# Telit2XBEE.net
KiCad netlist of a schematic drawn in EAGLE
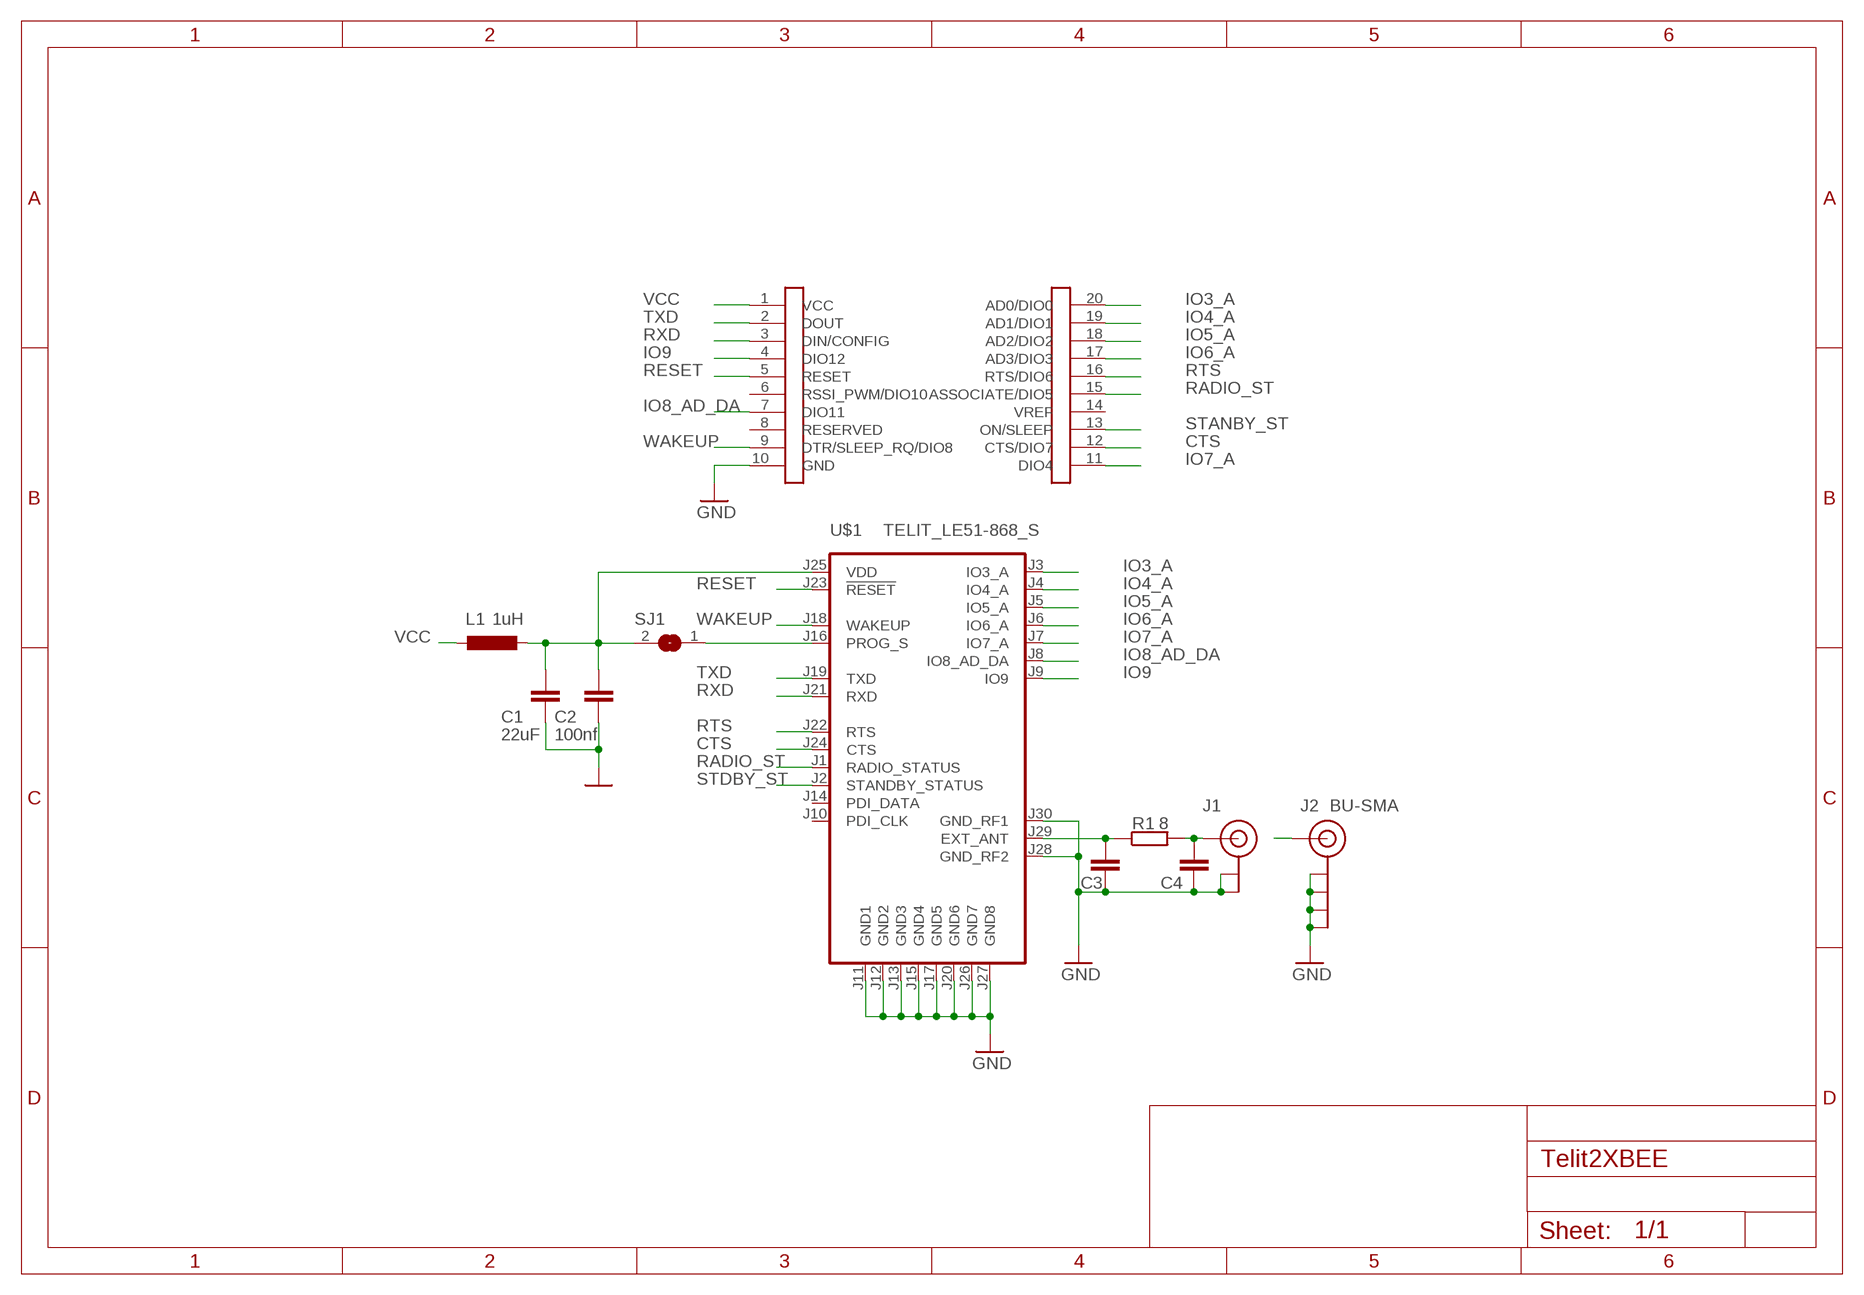
[diagram p0: schematic, sheet 1]

(export (version "E")
  (design (tool "Eeschema 10.0.6"))
  (components
    (comp (ref "C1")
      (value "22uF")
      (footprint "eagle-import:C1206")
      (libsource (lib "eagle-import") (part "C-EUC1206"))
    )
    (comp (ref "C2")
      (value "100nf")
      (footprint "eagle-import:C0805")
      (libsource (lib "eagle-import") (part "C-EUC0805"))
    )
    (comp (ref "C3")
      (value "C-EUC0201")
      (footprint "eagle-import:C0201")
      (libsource (lib "eagle-import") (part "C-EUC0201"))
    )
    (comp (ref "C4")
      (value "C-EUC0201")
      (footprint "eagle-import:C0201")
      (libsource (lib "eagle-import") (part "C-EUC0201"))
    )
    (comp (ref "J1")
      (value "U.FL")
      (footprint "eagle-import:U.FL_1PAD")
      (libsource (lib "eagle-import") (part "U.FL1PAD"))
    )
    (comp (ref "J2")
      (value "BU-SMA")
      (footprint "eagle-import:BU-SMA-G")
      (libsource (lib "eagle-import") (part "BU-SMA"))
    )
    (comp (ref "L1")
      (value "1uH")
      (footprint "eagle-import:COILCRAFT_LPS3015")
      (libsource (lib "eagle-import") (part "POWER_INDUCTOR3"))
    )
    (comp (ref "R1")
      (value "8")
      (footprint "eagle-import:R0201")
      (libsource (lib "eagle-import") (part "R-EU_R0201"))
    )
    (comp (ref "SJ1") (value "SJ") (footprint "eagle-import:SJ") (libsource (lib "eagle-import") (part "SJ")))
    (comp (ref "U$1")
      (value "TELIT_LE51-868_S")
      (footprint "eagle-import:TELIT_LE51")
      (libsource (lib "eagle-import") (part "TELIT_LE51"))
    )
    (comp (ref "U$2")
      (value "XBEE_PIN_HEADER")
      (footprint "eagle-import:XBEE_PIN_HEADER")
      (libsource (lib "eagle-import") (part "XBEE_PIN_HEADER"))
    )
  )
  (nets
    (net (code "1") (name "/CTS") (class "Default")
      (node (ref "U$1") (pin "J24") (pinfunction "CTS_J24") (pintype "bidirectional"))
      (node (ref "U$2") (pin "12") (pinfunction "CTS/DIO7_12") (pintype "bidirectional"))
    )
    (net (code "2") (name "/IO3_A") (class "Default")
      (node (ref "U$1") (pin "J3") (pinfunction "IO3_A_J3") (pintype "bidirectional"))
      (node (ref "U$2") (pin "20") (pinfunction "AD0/DIO0_20") (pintype "bidirectional"))
    )
    (net (code "3") (name "/IO4_A") (class "Default")
      (node (ref "U$1") (pin "J4") (pinfunction "IO4_A_J4") (pintype "bidirectional"))
      (node (ref "U$2") (pin "19") (pinfunction "AD1/DIO1_19") (pintype "bidirectional"))
    )
    (net (code "4") (name "/IO5_A") (class "Default")
      (node (ref "U$1") (pin "J5") (pinfunction "IO5_A_J5") (pintype "bidirectional"))
      (node (ref "U$2") (pin "18") (pinfunction "AD2/DIO2_18") (pintype "bidirectional"))
    )
    (net (code "5") (name "/IO6_A") (class "Default")
      (node (ref "U$1") (pin "J6") (pinfunction "IO6_A_J6") (pintype "bidirectional"))
      (node (ref "U$2") (pin "17") (pinfunction "AD3/DIO3_17") (pintype "bidirectional"))
    )
    (net (code "6") (name "/IO7_A") (class "Default")
      (node (ref "U$1") (pin "J7") (pinfunction "IO7_A_J7") (pintype "bidirectional"))
      (node (ref "U$2") (pin "11") (pinfunction "DIO4_11") (pintype "bidirectional"))
    )
    (net (code "7") (name "/IO8_AD_DA") (class "Default")
      (node (ref "U$1") (pin "J8") (pinfunction "IO8_AD_DA_J8") (pintype "bidirectional"))
      (node (ref "U$2") (pin "7") (pinfunction "DIO11_7") (pintype "bidirectional"))
    )
    (net (code "8") (name "/IO9") (class "Default")
      (node (ref "U$1") (pin "J9") (pinfunction "IO9_J9") (pintype "bidirectional"))
      (node (ref "U$2") (pin "4") (pinfunction "DIO12_4") (pintype "bidirectional"))
    )
    (net (code "9") (name "/N$2") (class "Default")
      (node (ref "C4") (pin "1") (pinfunction "1_1") (pintype "passive"))
      (node (ref "J1") (pin "P$3") (pinfunction "SIGNAL_P$3") (pintype "bidirectional"))
      (node (ref "J2") (pin "P$1") (pinfunction "SIGNAL_P$1") (pintype "bidirectional"))
      (node (ref "R1") (pin "2") (pinfunction "2_2") (pintype "passive"))
    )
    (net (code "10") (name "/RADIO_ST") (class "Default")
      (node (ref "U$1") (pin "J1") (pinfunction "RADIO_STATUS_J1") (pintype "bidirectional"))
      (node (ref "U$2") (pin "15") (pinfunction "ASSOCIATE/DIO5_15") (pintype "bidirectional"))
    )
    (net (code "11") (name "/RESET") (class "Default")
      (node (ref "U$1") (pin "J23") (pinfunction "~{RESET}_J23") (pintype "input"))
      (node (ref "U$2") (pin "5") (pinfunction "RESET_5") (pintype "bidirectional"))
    )
    (net (code "12") (name "/RTS") (class "Default")
      (node (ref "U$1") (pin "J22") (pinfunction "RTS_J22") (pintype "bidirectional"))
      (node (ref "U$2") (pin "16") (pinfunction "RTS/DIO6_16") (pintype "bidirectional"))
    )
    (net (code "13") (name "/RXD") (class "Default")
      (node (ref "U$1") (pin "J21") (pinfunction "RXD_J21") (pintype "output"))
      (node (ref "U$2") (pin "3") (pinfunction "DIN/CONFIG_3") (pintype "bidirectional"))
    )
    (net (code "14") (name "/STANBY_ST") (class "Default")
      (node (ref "U$2") (pin "13") (pinfunction "ON/SLEEP_13") (pintype "bidirectional"))
    )
    (net (code "15") (name "/STDBY_ST") (class "Default")
      (node (ref "U$1") (pin "J2") (pinfunction "STANDBY_STATUS_J2") (pintype "bidirectional"))
    )
    (net (code "16") (name "/TXD") (class "Default")
      (node (ref "U$1") (pin "J19") (pinfunction "TXD_J19") (pintype "input"))
      (node (ref "U$2") (pin "2") (pinfunction "DOUT_2") (pintype "bidirectional"))
    )
    (net (code "17") (name "/VCC") (class "Default")
      (node (ref "L1") (pin "P$1") (pinfunction "1_P$1") (pintype "passive"))
      (node (ref "U$2") (pin "1") (pinfunction "VCC_1") (pintype "bidirectional"))
    )
    (net (code "18") (name "/WAKEUP") (class "Default")
      (node (ref "U$1") (pin "J18") (pinfunction "WAKEUP_J18") (pintype "input"))
      (node (ref "U$2") (pin "9") (pinfunction "DTR/SLEEP_RQ/DIO8_9") (pintype "bidirectional"))
    )
    (net (code "19") (name "GND") (class "Default")
      (node (ref "C1") (pin "2") (pinfunction "2_2") (pintype "passive"))
      (node (ref "C2") (pin "2") (pinfunction "2_2") (pintype "passive"))
      (node (ref "C3") (pin "2") (pinfunction "2_2") (pintype "passive"))
      (node (ref "C4") (pin "2") (pinfunction "2_2") (pintype "passive"))
      (node (ref "J1") (pin "P$1") (pinfunction "GND_P$1") (pintype "bidirectional"))
      (node (ref "J1") (pin "P$2") (pinfunction "GND_P$2") (pintype "bidirectional"))
      (node (ref "J2") (pin "P$2") (pinfunction "GND_P$2") (pintype "bidirectional"))
      (node (ref "J2") (pin "P$3") (pinfunction "GND_P$3") (pintype "bidirectional"))
      (node (ref "J2") (pin "P$5") (pinfunction "GND_P$5") (pintype "bidirectional"))
      (node (ref "J2") (pin "P$6") (pinfunction "GND_P$6") (pintype "bidirectional"))
      (node (ref "U$1") (pin "J11") (pinfunction "GND1_J11") (pintype "power_in"))
      (node (ref "U$1") (pin "J12") (pinfunction "GND2_J12") (pintype "power_in"))
      (node (ref "U$1") (pin "J13") (pinfunction "GND3_J13") (pintype "power_in"))
      (node (ref "U$1") (pin "J15") (pinfunction "GND4_J15") (pintype "power_in"))
      (node (ref "U$1") (pin "J17") (pinfunction "GND5_J17") (pintype "power_in"))
      (node (ref "U$1") (pin "J20") (pinfunction "GND6_J20") (pintype "power_in"))
      (node (ref "U$1") (pin "J26") (pinfunction "GND7_J26") (pintype "power_in"))
      (node (ref "U$1") (pin "J27") (pinfunction "GND8_J27") (pintype "power_in"))
      (node (ref "U$1") (pin "J28") (pinfunction "GND_RF2_J28") (pintype "bidirectional"))
      (node (ref "U$1") (pin "J30") (pinfunction "GND_RF1_J30") (pintype "bidirectional"))
      (node (ref "U$2") (pin "10") (pinfunction "GND_10") (pintype "bidirectional"))
    )
    (net (code "20") (name "Net-(L1-2)") (class "Default")
      (node (ref "C1") (pin "1") (pinfunction "1_1") (pintype "passive"))
      (node (ref "C2") (pin "1") (pinfunction "1_1") (pintype "passive"))
      (node (ref "L1") (pin "P$2") (pinfunction "2_P$2") (pintype "passive"))
      (node (ref "SJ1") (pin "2") (pinfunction "2_2") (pintype "passive"))
      (node (ref "U$1") (pin "J25") (pinfunction "VDD_J25") (pintype "power_in"))
    )
    (net (code "21") (name "Net-(U$1-EXT_ANT)") (class "Default")
      (node (ref "C3") (pin "1") (pinfunction "1_1") (pintype "passive"))
      (node (ref "R1") (pin "1") (pinfunction "1_1") (pintype "passive"))
      (node (ref "U$1") (pin "J29") (pinfunction "EXT_ANT_J29") (pintype "bidirectional"))
    )
    (net (code "22") (name "Net-(U$1-PROG_S)") (class "Default")
      (node (ref "SJ1") (pin "1") (pinfunction "1_1") (pintype "passive"))
      (node (ref "U$1") (pin "J16") (pinfunction "PROG_S_J16") (pintype "input"))
    )
    (net (code "23") (name "unconnected-(U$1-PDI_CLK-PadJ10)") (class "Default")
      (node (ref "U$1") (pin "J10") (pinfunction "PDI_CLK_J10") (pintype "bidirectional"))
    )
    (net (code "24") (name "unconnected-(U$1-PDI_DATA-PadJ14)") (class "Default")
      (node (ref "U$1") (pin "J14") (pinfunction "PDI_DATA_J14") (pintype "bidirectional"))
    )
    (net (code "25") (name "unconnected-(U$2-RESERVED-Pad8)") (class "Default")
      (node (ref "U$2") (pin "8") (pinfunction "RESERVED_8") (pintype "bidirectional"))
    )
    (net (code "26") (name "unconnected-(U$2-RSSI_PWM{slash}DIO10-Pad6)") (class "Default")
      (node (ref "U$2") (pin "6") (pinfunction "RSSI_PWM/DIO10_6") (pintype "bidirectional"))
    )
    (net (code "27") (name "unconnected-(U$2-VREF-Pad14)") (class "Default")
      (node (ref "U$2") (pin "14") (pinfunction "VREF_14") (pintype "bidirectional"))
    )
  )
)
